# Power_Supply.net
KiCad netlist of a schematic drawn in Altium Designer
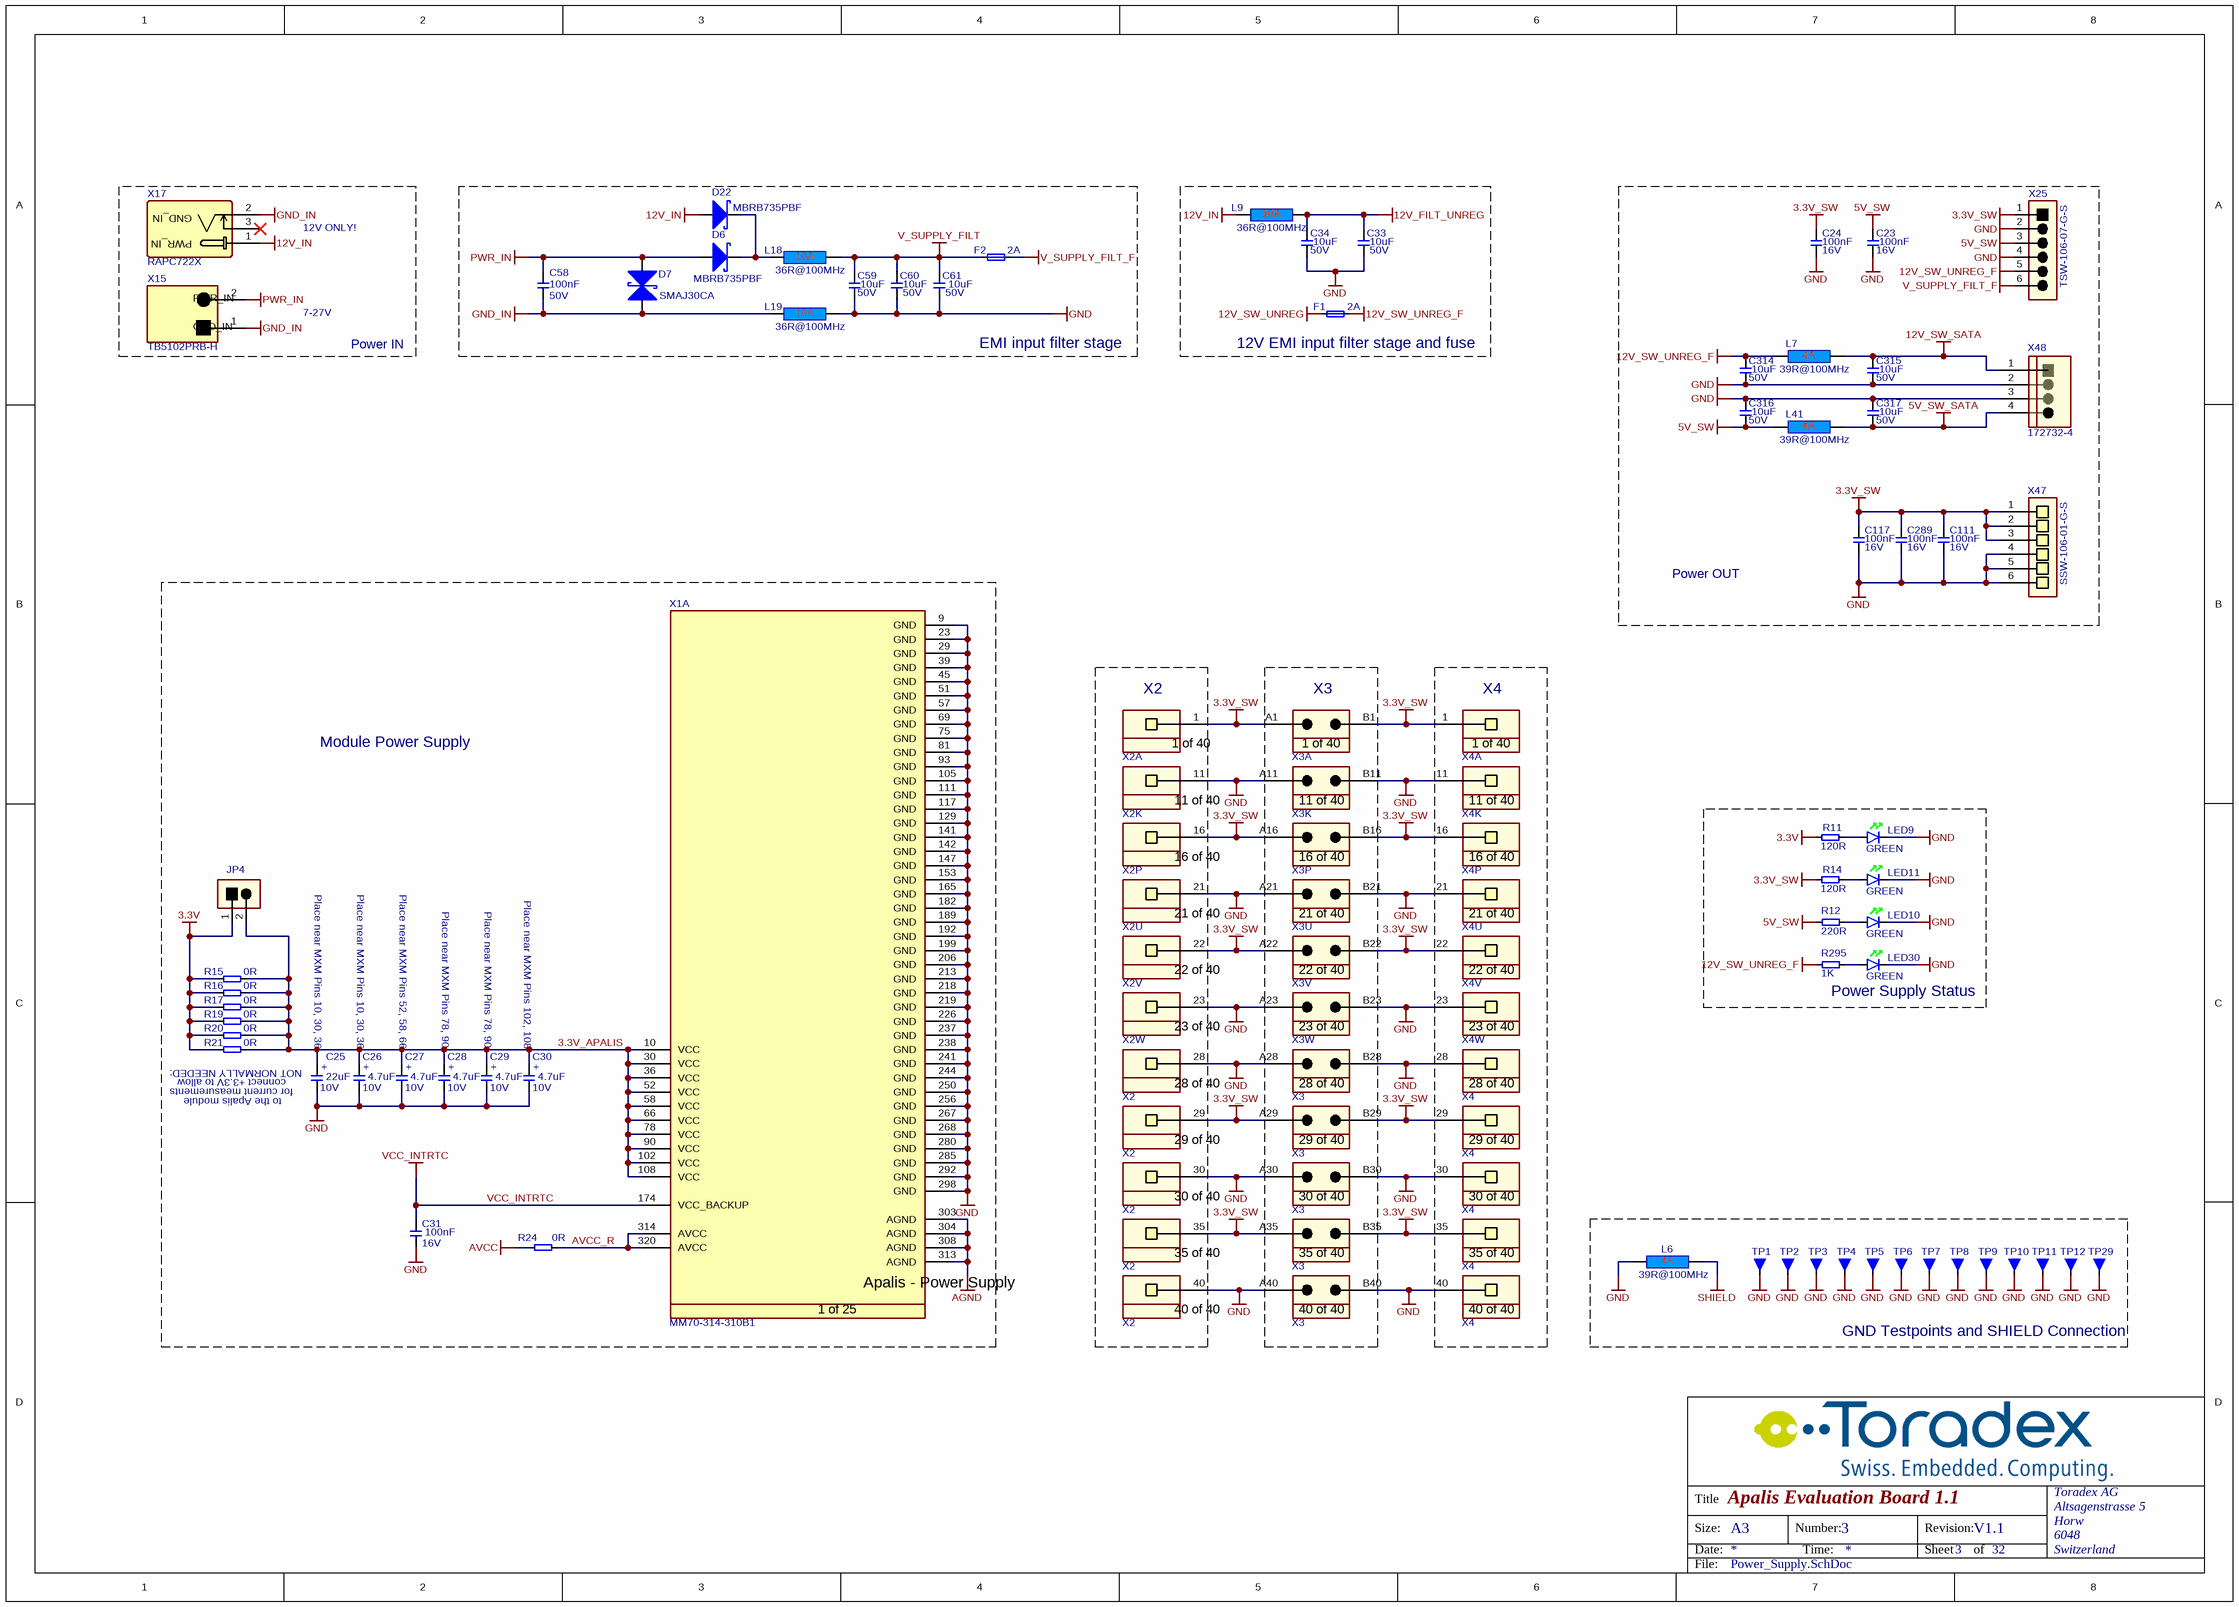
[diagram p0: Power_Supply.SchDoc]

(export (version "E")
  (design (tool "Eeschema 10.0.6"))
  (components
    (comp (ref "C23")
      (value "100nF")
      (footprint "T_CAPC0603X33N")
      (description "Capacitor Ceramic X7R 100nF 16V 10% 0603")
      (fields (field (name "TOLERANCE") "10%") (field (name "RATING") "16V"))
      (libsource (lib "Apalis Evaluation Board") (part "C-X7R-100nF-16V-10%-0603"))
    )
    (comp (ref "C24")
      (value "100nF")
      (footprint "T_CAPC0603X33N")
      (description "Capacitor Ceramic X7R 100nF 16V 10% 0603")
      (fields (field (name "TOLERANCE") "10%") (field (name "RATING") "16V"))
      (libsource (lib "Apalis Evaluation Board") (part "C-X7R-100nF-16V-10%-0603"))
    )
    (comp (ref "C25")
      (value "22uF")
      (footprint "CAPMP3528X210N")
      (description "Capacitor TA 22uF 10V 20% 3528")
      (fields (field (name "TOLERANCE") "20%") (field (name "RATING") "10V"))
      (libsource (lib "Apalis Evaluation Board") (part "C-TA-22uF-10V-20%-3528"))
    )
    (comp (ref "C26")
      (value "4.7uF")
      (footprint "T_CAPMP3216X180N")
      (description "Capacitor TA 4.7uF 10V 20% 3216")
      (fields (field (name "TOLERANCE") "20%") (field (name "RATING") "10V"))
      (libsource (lib "Apalis Evaluation Board") (part "C-TA-4.7uF-10V-20%-3216"))
    )
    (comp (ref "C27")
      (value "4.7uF")
      (footprint "T_CAPMP3216X180N")
      (description "Capacitor TA 4.7uF 10V 20% 3216")
      (fields (field (name "TOLERANCE") "20%") (field (name "RATING") "10V"))
      (libsource (lib "Apalis Evaluation Board") (part "C-TA-4.7uF-10V-20%-3216"))
    )
    (comp (ref "C28")
      (value "4.7uF")
      (footprint "T_CAPMP3216X180N")
      (description "Capacitor TA 4.7uF 10V 20% 3216")
      (fields (field (name "TOLERANCE") "20%") (field (name "RATING") "10V"))
      (libsource (lib "Apalis Evaluation Board") (part "C-TA-4.7uF-10V-20%-3216"))
    )
    (comp (ref "C29")
      (value "4.7uF")
      (footprint "T_CAPMP3216X180N")
      (description "Capacitor TA 4.7uF 10V 20% 3216")
      (fields (field (name "TOLERANCE") "20%") (field (name "RATING") "10V"))
      (libsource (lib "Apalis Evaluation Board") (part "C-TA-4.7uF-10V-20%-3216"))
    )
    (comp (ref "C30")
      (value "4.7uF")
      (footprint "T_CAPMP3216X180N")
      (description "Capacitor TA 4.7uF 10V 20% 3216")
      (fields (field (name "TOLERANCE") "20%") (field (name "RATING") "10V"))
      (libsource (lib "Apalis Evaluation Board") (part "C-TA-4.7uF-10V-20%-3216"))
    )
    (comp (ref "C31")
      (value "100nF")
      (footprint "T_CAPC0603X33N")
      (description "Capacitor Ceramic X7R 100nF 16V 10% 0603")
      (fields (field (name "TOLERANCE") "10%") (field (name "RATING") "16V"))
      (libsource (lib "Apalis Evaluation Board") (part "C-X7R-100nF-16V-10%-0603"))
    )
    (comp (ref "C33")
      (value "10uF")
      (footprint "CAPC3225X160N")
      (description "Capacitor Ceramic X5R 10uF 50V 20% 1210")
      (fields (field (name "TOLERANCE") "20%") (field (name "RATING") "50V"))
      (libsource (lib "Apalis Evaluation Board") (part "C-X5R-10uF-50V-20%-1210"))
    )
    (comp (ref "C34")
      (value "10uF")
      (footprint "CAPC3225X160N")
      (description "Capacitor Ceramic X5R 10uF 50V 20% 1210")
      (fields (field (name "TOLERANCE") "20%") (field (name "RATING") "50V"))
      (libsource (lib "Apalis Evaluation Board") (part "C-X5R-10uF-50V-20%-1210"))
    )
    (comp (ref "C58")
      (value "100nF")
      (footprint "T_CAPC0603X33N")
      (description "Capacitor Ceramic X7R 100nF 50V 20% 0603")
      (fields (field (name "TOLERANCE") "20%") (field (name "RATING") "50V"))
      (libsource (lib "Apalis Evaluation Board") (part "C-X7R-100nF-50V-20%-0603"))
    )
    (comp (ref "C59")
      (value "10uF")
      (footprint "CAPC3225X160N")
      (description "Capacitor Ceramic X5R 10uF 50V 20% 1210")
      (fields (field (name "TOLERANCE") "20%") (field (name "RATING") "50V"))
      (libsource (lib "Apalis Evaluation Board") (part "C-X5R-10uF-50V-20%-1210"))
    )
    (comp (ref "C60")
      (value "10uF")
      (footprint "CAPC3225X160N")
      (description "Capacitor Ceramic X5R 10uF 50V 20% 1210")
      (fields (field (name "TOLERANCE") "20%") (field (name "RATING") "50V"))
      (libsource (lib "Apalis Evaluation Board") (part "C-X5R-10uF-50V-20%-1210"))
    )
    (comp (ref "C61")
      (value "10uF")
      (footprint "CAPC3225X160N")
      (description "Capacitor Ceramic X5R 10uF 50V 20% 1210")
      (fields (field (name "TOLERANCE") "20%") (field (name "RATING") "50V"))
      (libsource (lib "Apalis Evaluation Board") (part "C-X5R-10uF-50V-20%-1210"))
    )
    (comp (ref "C111")
      (value "100nF")
      (footprint "T_CAPC0603X33N")
      (description "Capacitor Ceramic X7R 100nF 16V 10% 0603")
      (fields (field (name "TOLERANCE") "10%") (field (name "RATING") "16V"))
      (libsource (lib "Apalis Evaluation Board") (part "C-X7R-100nF-16V-10%-0603"))
    )
    (comp (ref "C117")
      (value "100nF")
      (footprint "T_CAPC0603X33N")
      (description "Capacitor Ceramic X7R 100nF 16V 10% 0603")
      (fields (field (name "TOLERANCE") "10%") (field (name "RATING") "16V"))
      (libsource (lib "Apalis Evaluation Board") (part "C-X7R-100nF-16V-10%-0603"))
    )
    (comp (ref "C289")
      (value "100nF")
      (footprint "T_CAPC0603X33N")
      (description "Capacitor Ceramic X7R 100nF 16V 10% 0603")
      (fields (field (name "TOLERANCE") "10%") (field (name "RATING") "16V"))
      (libsource (lib "Apalis Evaluation Board") (part "C-X7R-100nF-16V-10%-0603"))
    )
    (comp (ref "C314")
      (value "10uF")
      (footprint "CAPC3225X160N")
      (description "Capacitor Ceramic X5R 10uF 50V 20% 1210")
      (fields (field (name "TOLERANCE") "20%") (field (name "RATING") "50V"))
      (libsource (lib "Apalis Evaluation Board") (part "C-X5R-10uF-50V-20%-1210"))
    )
    (comp (ref "C315")
      (value "10uF")
      (footprint "CAPC3225X160N")
      (description "Capacitor Ceramic X5R 10uF 50V 20% 1210")
      (fields (field (name "TOLERANCE") "20%") (field (name "RATING") "50V"))
      (libsource (lib "Apalis Evaluation Board") (part "C-X5R-10uF-50V-20%-1210"))
    )
    (comp (ref "C316")
      (value "10uF")
      (footprint "CAPC3225X160N")
      (description "Capacitor Ceramic X5R 10uF 50V 20% 1210")
      (fields (field (name "TOLERANCE") "20%") (field (name "RATING") "50V"))
      (libsource (lib "Apalis Evaluation Board") (part "C-X5R-10uF-50V-20%-1210"))
    )
    (comp (ref "C317")
      (value "10uF")
      (footprint "CAPC3225X160N")
      (description "Capacitor Ceramic X5R 10uF 50V 20% 1210")
      (fields (field (name "TOLERANCE") "20%") (field (name "RATING") "50V"))
      (libsource (lib "Apalis Evaluation Board") (part "C-X5R-10uF-50V-20%-1210"))
    )
    (comp (ref "D6")
      (value "MBRB735PBF")
      (footprint "T_VISHAY_MBRB735PBF")
      (description "MBRB735PBF Schottky Diode")
      (fields (field (name "MANUFACTURER PART NO.") "MBRB735PBF"))
      (libsource (lib "Apalis Evaluation Board") (part "D-VISHAY-MBRB735PBF"))
    )
    (comp (ref "D7")
      (value "D-Littelfuse-SMAJ30CA-Schottky")
      (footprint "T_LITTLEFUSE_SMAJ30CA")
      (description "Bidirectional ESD protection")
      (fields (field (name "MANUFACTURER PART NO.") "SMAJ30CA"))
      (libsource (lib "Apalis Evaluation Board") (part "D-Littelfuse-SMAJ30CA-Schottky"))
    )
    (comp (ref "D22")
      (value "MBRB735PBF")
      (footprint "T_VISHAY_MBRB735PBF")
      (description "MBRB735PBF Schottky Diode")
      (fields (field (name "MANUFACTURER PART NO.") "MBRB735PBF"))
      (libsource (lib "Apalis Evaluation Board") (part "D-VISHAY-MBRB735PBF"))
    )
    (comp (ref "F1")
      (value "2A")
      (footprint "T_Littelfuse_0458")
      (description "Fuse 2A Fast")
      (fields (field (name "MANUFACTURER PART NO.") "0458002"))
      (libsource (lib "Apalis Evaluation Board") (part "F-Littelfuse-0458002"))
    )
    (comp (ref "F2")
      (value "2A")
      (footprint "T_Littelfuse_0458")
      (description "Fuse 2A Fast")
      (fields (field (name "MANUFACTURER PART NO.") "0458002"))
      (libsource (lib "Apalis Evaluation Board") (part "F-Littelfuse-0458002"))
    )
    (comp (ref "JP4")
      (value "TSW-101-07-G-D")
      (footprint "T_Samtec_TSW-101-07-G-D")
      (description "Header male, 1x2 Pins, 2.54 mm pitch")
      (libsource (lib "Apalis Evaluation Board") (part "CON-Samtec-TSW-101-07-G-D"))
    )
    (comp (ref "L6")
      (value "39R@100MHz")
      (footprint "INDC2013X130N")
      (description "39R@100MHz 4A EMI FILTER")
      (fields (field (name "TOLERANCE") "25%"))
      (libsource (lib "Apalis Evaluation Board") (part "L-Panasonic-EXC-ML20A390U-39R@100MHz-4A-25%-0805"))
    )
    (comp (ref "L7")
      (value "39R@100MHz")
      (footprint "INDC2013X130N")
      (description "39R@100MHz 4A EMI FILTER")
      (fields (field (name "TOLERANCE") "25%"))
      (libsource (lib "Apalis Evaluation Board") (part "L-Panasonic-EXC-ML20A390U-39R@100MHz-4A-25%-0805"))
    )
    (comp (ref "L9")
      (value "36R@100MHz")
      (footprint "T_Laird_35F0121-0SR-10")
      (description "Power Supply FB 10A")
      (fields (field (name "TOLERANCE") "25%"))
      (libsource (lib "Apalis Evaluation Board") (part "L-Laird-35F0121-0SR-10-10A-25%"))
    )
    (comp (ref "L18")
      (value "36R@100MHz")
      (footprint "T_Laird_35F0121-0SR-10")
      (description "Power Supply FB 10A")
      (fields (field (name "TOLERANCE") "25%"))
      (libsource (lib "Apalis Evaluation Board") (part "L-Laird-35F0121-0SR-10-10A-25%"))
    )
    (comp (ref "L19")
      (value "36R@100MHz")
      (footprint "T_Laird_35F0121-0SR-10")
      (description "Power Supply FB 10A")
      (fields (field (name "TOLERANCE") "25%"))
      (libsource (lib "Apalis Evaluation Board") (part "L-Laird-35F0121-0SR-10-10A-25%"))
    )
    (comp (ref "L41")
      (value "39R@100MHz")
      (footprint "INDC2013X130N")
      (description "39R@100MHz 4A EMI FILTER")
      (fields (field (name "TOLERANCE") "25%"))
      (libsource (lib "Apalis Evaluation Board") (part "L-Panasonic-EXC-ML20A390U-39R@100MHz-4A-25%-0805"))
    )
    (comp (ref "LED9")
      (value "LG T670-K1L2-1")
      (footprint "T_Osram_T670_GREEN")
      (description "LED green Osram LG T670-K1L2-1")
      (fields (field (name "COLOR") "GREEN"))
      (libsource (lib "Apalis Evaluation Board") (part "LED-Osram-T670-K1L2-1"))
    )
    (comp (ref "LED10")
      (value "LG T670-K1L2-1")
      (footprint "T_Osram_T670_GREEN")
      (description "LED green Osram LG T670-K1L2-1")
      (fields (field (name "COLOR") "GREEN"))
      (libsource (lib "Apalis Evaluation Board") (part "LED-Osram-T670-K1L2-1"))
    )
    (comp (ref "LED11")
      (value "LG T670-K1L2-1")
      (footprint "T_Osram_T670_GREEN")
      (description "LED green Osram LG T670-K1L2-1")
      (fields (field (name "COLOR") "GREEN"))
      (libsource (lib "Apalis Evaluation Board") (part "LED-Osram-T670-K1L2-1"))
    )
    (comp (ref "LED30")
      (value "LG T670-K1L2-1")
      (footprint "T_Osram_T670_GREEN")
      (description "LED green Osram LG T670-K1L2-1")
      (fields (field (name "COLOR") "GREEN"))
      (libsource (lib "Apalis Evaluation Board") (part "LED-Osram-T670-K1L2-1"))
    )
    (comp (ref "R11")
      (value "120R")
      (footprint "T_RESC0603X30N")
      (description "Resistor 120 ohm 63mW 5% 0603")
      (fields (field (name "TOLERANCE") "5%"))
      (libsource (lib "Apalis Evaluation Board") (part "R-120R-63mW-5%-0603"))
    )
    (comp (ref "R12")
      (value "220R")
      (footprint "T_RESC0603X30N")
      (description "Resistor 220 ohm 63mW 5% 0603")
      (fields (field (name "TOLERANCE") "5%"))
      (libsource (lib "Apalis Evaluation Board") (part "R-220R-63mW-5%-0603"))
    )
    (comp (ref "R14")
      (value "120R")
      (footprint "T_RESC0603X30N")
      (description "Resistor 120 ohm 63mW 5% 0603")
      (fields (field (name "TOLERANCE") "5%"))
      (libsource (lib "Apalis Evaluation Board") (part "R-120R-63mW-5%-0603"))
    )
    (comp (ref "R15")
      (value "0R")
      (footprint "T_RESC3216X760N")
      (description "Resistor 0 ohm 63mW 1% 1206")
      (fields (field (name "TOLERANCE") "1%"))
      (libsource (lib "Apalis Evaluation Board") (part "R-0R-63mW-1%-1206"))
    )
    (comp (ref "R16")
      (value "0R")
      (footprint "T_RESC3216X760N")
      (description "Resistor 0 ohm 63mW 1% 1206")
      (fields (field (name "TOLERANCE") "1%"))
      (libsource (lib "Apalis Evaluation Board") (part "R-0R-63mW-1%-1206"))
    )
    (comp (ref "R17")
      (value "0R")
      (footprint "T_RESC3216X760N")
      (description "Resistor 0 ohm 63mW 1% 1206")
      (fields (field (name "TOLERANCE") "1%"))
      (libsource (lib "Apalis Evaluation Board") (part "R-0R-63mW-1%-1206"))
    )
    (comp (ref "R19")
      (value "0R")
      (footprint "T_RESC3216X760N")
      (description "Resistor 0 ohm 63mW 1% 1206")
      (fields (field (name "TOLERANCE") "1%"))
      (libsource (lib "Apalis Evaluation Board") (part "R-0R-63mW-1%-1206"))
    )
    (comp (ref "R20")
      (value "0R")
      (footprint "T_RESC3216X760N")
      (description "Resistor 0 ohm 63mW 1% 1206")
      (fields (field (name "TOLERANCE") "1%"))
      (libsource (lib "Apalis Evaluation Board") (part "R-0R-63mW-1%-1206"))
    )
    (comp (ref "R21")
      (value "0R")
      (footprint "T_RESC3216X760N")
      (description "Resistor 0 ohm 63mW 1% 1206")
      (fields (field (name "TOLERANCE") "1%"))
      (libsource (lib "Apalis Evaluation Board") (part "R-0R-63mW-1%-1206"))
    )
    (comp (ref "R24")
      (value "0R")
      (footprint "T_RESC0603X30N")
      (description "Resistor 0 ohm 63mW 1% 0603")
      (fields (field (name "TOLERANCE") "1%"))
      (libsource (lib "Apalis Evaluation Board") (part "R-0R-63mW-1%-0603"))
    )
    (comp (ref "R295")
      (value "1K")
      (footprint "T_RESC0603X30N")
      (description "Resistor 1 Kohm 63mW 5% 0603")
      (fields (field (name "TOLERANCE") "5%"))
      (libsource (lib "Apalis Evaluation Board") (part "R-1KR-63mW-5%-0603"))
    )
    (comp (ref "TP1")
      (value "5011")
      (footprint "T_TP-THT - EYE")
      (description "Testpin Eye TH")
      (libsource (lib "Apalis Evaluation Board") (part "TP-Keystone-5011"))
    )
    (comp (ref "TP2")
      (value "5011")
      (footprint "T_TP-THT - EYE")
      (description "Testpin Eye TH")
      (libsource (lib "Apalis Evaluation Board") (part "TP-Keystone-5011"))
    )
    (comp (ref "TP3")
      (value "5011")
      (footprint "T_TP-THT - EYE")
      (description "Testpin Eye TH")
      (libsource (lib "Apalis Evaluation Board") (part "TP-Keystone-5011"))
    )
    (comp (ref "TP4")
      (value "5011")
      (footprint "T_TP-THT - EYE")
      (description "Testpin Eye TH")
      (libsource (lib "Apalis Evaluation Board") (part "TP-Keystone-5011"))
    )
    (comp (ref "TP5")
      (value "5011")
      (footprint "T_TP-THT - EYE")
      (description "Testpin Eye TH")
      (libsource (lib "Apalis Evaluation Board") (part "TP-Keystone-5011"))
    )
    (comp (ref "TP6")
      (value "5011")
      (footprint "T_TP-THT - EYE")
      (description "Testpin Eye TH")
      (libsource (lib "Apalis Evaluation Board") (part "TP-Keystone-5011"))
    )
    (comp (ref "TP7")
      (value "5011")
      (footprint "T_TP-THT - EYE")
      (description "Testpin Eye TH")
      (libsource (lib "Apalis Evaluation Board") (part "TP-Keystone-5011"))
    )
    (comp (ref "TP8")
      (value "5011")
      (footprint "T_TP-THT - EYE")
      (description "Testpin Eye TH")
      (libsource (lib "Apalis Evaluation Board") (part "TP-Keystone-5011"))
    )
    (comp (ref "TP9")
      (value "5011")
      (footprint "T_TP-THT - EYE")
      (description "Testpin Eye TH")
      (libsource (lib "Apalis Evaluation Board") (part "TP-Keystone-5011"))
    )
    (comp (ref "TP10")
      (value "5011")
      (footprint "T_TP-THT - EYE")
      (description "Testpin Eye TH")
      (libsource (lib "Apalis Evaluation Board") (part "TP-Keystone-5011"))
    )
    (comp (ref "TP11")
      (value "5011")
      (footprint "T_TP-THT - EYE")
      (description "Testpin Eye TH")
      (libsource (lib "Apalis Evaluation Board") (part "TP-Keystone-5011"))
    )
    (comp (ref "TP12")
      (value "5011")
      (footprint "T_TP-THT - EYE")
      (description "Testpin Eye TH")
      (libsource (lib "Apalis Evaluation Board") (part "TP-Keystone-5011"))
    )
    (comp (ref "TP29")
      (value "5011")
      (footprint "T_TP-THT - EYE")
      (description "Testpin Eye TH")
      (libsource (lib "Apalis Evaluation Board") (part "TP-Keystone-5011"))
    )
    (comp (ref "X1")
      (value "CON-JAE-MM70-314-310B1-314-0.5mm")
      (footprint "T_JAE_MM70-314-310B1")
      (description "MXM3 Connector")
      (fields (field (name "MANUFACTURER PART NO.") "MM70-314-310B1"))
      (libsource (lib "Apalis Evaluation Board") (part "CON-JAE-MM70-314-310B1-314-0.5mm"))
    )
    (comp (ref "X2")
      (value "SSW-110-01-G-S")
      (footprint "T_Samtec_SSW-110-01-G-S")
      (description "Receptacle Female Socket 1x40 pin 2.54mm pitch")
      (libsource (lib "Apalis Evaluation Board") (part "CON-Samtec-SSW-110-01-G-S"))
    )
    (comp (ref "X3")
      (value "TSW-110-07-G-D")
      (footprint "T_Samtec_TSW-110-07-G-D")
      (description "Header 2x40 pin 2.54mm pitch")
      (libsource (lib "Apalis Evaluation Board") (part "CON-Samtec-TSW-110-07-G-D"))
    )
    (comp (ref "X4")
      (value "SSW-110-01-G-S")
      (footprint "T_Samtec_SSW-110-01-G-S")
      (description "Receptacle Female Socket 1x40 pin 2.54mm pitch")
      (libsource (lib "") (part "CON-Samtec-SSW-110-01-G-S_1"))
    )
    (comp (ref "X15")
      (value "TB5102PRB-H")
      (footprint "T_AUK_TB5102PRB-H")
      (description "Power Connector")
      (fields (field (name "MANUFACTURER PART NO.") "TB5102PRB-H"))
      (libsource (lib "Apalis Evaluation Board") (part "CON-AUK-TB5102PRB-H-1x2-50.8mm"))
    )
    (comp (ref "X17")
      (value "RAPC722X")
      (footprint "T_DCJ20-0014TB-L")
      (description "Power Jack")
      (fields (field (name "MANUFACTURER PART NO.") "RAPC722X"))
      (libsource (lib "Apalis Evaluation Board") (part "CON-SWC-RAPC722X"))
    )
    (comp (ref "X25")
      (value "TSW-106-07-G-S")
      (footprint "T_samtech_TSW-106-07-G-S")
      (description "Header male, 1X6 Pins, 2.54 mm pitch")
      (fields (field (name "MANUFACTURER PART NO.") "TSW-106-07-G-S"))
      (libsource (lib "Apalis Evaluation Board") (part "CON-Samtec-TSW-106-07-G-S"))
    )
    (comp (ref "X47")
      (value "SSW-106-01-G-S")
      (footprint "T_samtech_SSW-106-01-G-S")
      (description "Receptacle Female Socket, 1x6 Pins, 2.54mm pitch")
      (fields (field (name "MANUFACTURER PART NO.") "SSW-106-01-G-S"))
      (libsource (lib "Apalis Evaluation Board") (part "CON-Samtec-SSW-106-01-G-S"))
    )
    (comp (ref "X48")
      (value "172732-4")
      (footprint "T_TE_172732-4")
      (description "Header 4 pos Vert Kink Pin")
      (fields (field (name "MANUFACTURER PART NO.") "172732-4"))
      (libsource (lib "Apalis Evaluation Board") (part "CON-TECon-172732-4"))
    )
  )
  (nets
    (net (code "1") (name "/3.3V_APALIS") (class "Default")
      (node (ref "C25") (pin "1") (pinfunction "1_1") (pintype "passive"))
      (node (ref "C26") (pin "1") (pinfunction "1_1") (pintype "passive"))
      (node (ref "C27") (pin "1") (pinfunction "1_1") (pintype "passive"))
      (node (ref "C28") (pin "1") (pinfunction "1_1") (pintype "passive"))
      (node (ref "C29") (pin "1") (pinfunction "1_1") (pintype "passive"))
      (node (ref "C30") (pin "1") (pinfunction "1_1") (pintype "passive"))
      (node (ref "JP4") (pin "2") (pinfunction "2_2") (pintype "passive"))
      (node (ref "R15") (pin "2") (pinfunction "2_2") (pintype "passive"))
      (node (ref "R16") (pin "2") (pinfunction "2_2") (pintype "passive"))
      (node (ref "R17") (pin "2") (pinfunction "2_2") (pintype "passive"))
      (node (ref "R19") (pin "2") (pinfunction "2_2") (pintype "passive"))
      (node (ref "R20") (pin "2") (pinfunction "2_2") (pintype "passive"))
      (node (ref "R21") (pin "2") (pinfunction "2_2") (pintype "passive"))
      (node (ref "X1") (pin "10") (pinfunction "VCC_10") (pintype "passive"))
      (node (ref "X1") (pin "102") (pinfunction "VCC_102") (pintype "passive"))
      (node (ref "X1") (pin "108") (pinfunction "VCC_108") (pintype "passive"))
      (node (ref "X1") (pin "30") (pinfunction "VCC_30") (pintype "passive"))
      (node (ref "X1") (pin "36") (pinfunction "VCC_36") (pintype "passive"))
      (node (ref "X1") (pin "52") (pinfunction "VCC_52") (pintype "passive"))
      (node (ref "X1") (pin "58") (pinfunction "VCC_58") (pintype "passive"))
      (node (ref "X1") (pin "66") (pinfunction "VCC_66") (pintype "passive"))
      (node (ref "X1") (pin "78") (pinfunction "VCC_78") (pintype "passive"))
      (node (ref "X1") (pin "90") (pinfunction "VCC_90") (pintype "passive"))
    )
    (net (code "2") (name "/AVCC_R") (class "Default")
      (node (ref "R24") (pin "2") (pinfunction "2_2") (pintype "passive"))
      (node (ref "X1") (pin "314") (pinfunction "AVCC_314") (pintype "power_in"))
      (node (ref "X1") (pin "320") (pinfunction "AVCC_320") (pintype "passive"))
    )
    (net (code "3") (name "3.3V") (class "Default")
      (node (ref "JP4") (pin "1") (pinfunction "1_1") (pintype "passive"))
      (node (ref "R11") (pin "1") (pinfunction "1_1") (pintype "passive"))
      (node (ref "R15") (pin "1") (pinfunction "1_1") (pintype "passive"))
      (node (ref "R16") (pin "1") (pinfunction "1_1") (pintype "passive"))
      (node (ref "R17") (pin "1") (pinfunction "1_1") (pintype "passive"))
      (node (ref "R19") (pin "1") (pinfunction "1_1") (pintype "passive"))
      (node (ref "R20") (pin "1") (pinfunction "1_1") (pintype "passive"))
      (node (ref "R21") (pin "1") (pinfunction "1_1") (pintype "passive"))
    )
    (net (code "4") (name "3.3V_SW") (class "Default")
      (node (ref "C111") (pin "2") (pinfunction "2_2") (pintype "passive"))
      (node (ref "C117") (pin "2") (pinfunction "2_2") (pintype "passive"))
      (node (ref "C24") (pin "2") (pinfunction "2_2") (pintype "passive"))
      (node (ref "C289") (pin "2") (pinfunction "2_2") (pintype "passive"))
      (node (ref "R14") (pin "1") (pinfunction "1_1") (pintype "passive"))
      (node (ref "X2") (pin "1") (pinfunction "1_1") (pintype "passive"))
      (node (ref "X2") (pin "16") (pinfunction "16_16") (pintype "passive"))
      (node (ref "X2") (pin "22") (pinfunction "22_22") (pintype "passive"))
      (node (ref "X2") (pin "29") (pinfunction "29_29") (pintype "passive"))
      (node (ref "X2") (pin "35") (pinfunction "35_35") (pintype "passive"))
      (node (ref "X25") (pin "1") (pinfunction "1_1") (pintype "passive"))
      (node (ref "X3") (pin "A1") (pinfunction "A1_A1") (pintype "passive"))
      (node (ref "X3") (pin "A16") (pinfunction "A16_A16") (pintype "passive"))
      (node (ref "X3") (pin "A22") (pinfunction "A22_A22") (pintype "passive"))
      (node (ref "X3") (pin "A29") (pinfunction "A29_A29") (pintype "passive"))
      (node (ref "X3") (pin "A35") (pinfunction "A35_A35") (pintype "passive"))
      (node (ref "X3") (pin "B1") (pinfunction "B1_B1") (pintype "passive"))
      (node (ref "X3") (pin "B16") (pinfunction "B16_B16") (pintype "passive"))
      (node (ref "X3") (pin "B22") (pinfunction "B22_B22") (pintype "passive"))
      (node (ref "X3") (pin "B29") (pinfunction "B29_B29") (pintype "passive"))
      (node (ref "X3") (pin "B35") (pinfunction "B35_B35") (pintype "passive"))
      (node (ref "X4") (pin "1") (pinfunction "1_1") (pintype "passive"))
      (node (ref "X4") (pin "16") (pinfunction "16_16") (pintype "passive"))
      (node (ref "X4") (pin "22") (pinfunction "22_22") (pintype "passive"))
      (node (ref "X4") (pin "29") (pinfunction "29_29") (pintype "passive"))
      (node (ref "X4") (pin "35") (pinfunction "35_35") (pintype "passive"))
      (node (ref "X47") (pin "1") (pinfunction "1_1") (pintype "passive"))
      (node (ref "X47") (pin "2") (pinfunction "2_2") (pintype "passive"))
      (node (ref "X47") (pin "3") (pinfunction "3_3") (pintype "passive"))
    )
    (net (code "5") (name "5V_SW") (class "Default")
      (node (ref "C23") (pin "1") (pinfunction "1_1") (pintype "passive"))
      (node (ref "C316") (pin "1") (pinfunction "1_1") (pintype "passive"))
      (node (ref "L41") (pin "1") (pinfunction "1_1") (pintype "passive"))
      (node (ref "R12") (pin "1") (pinfunction "1_1") (pintype "passive"))
      (node (ref "X25") (pin "3") (pinfunction "3_3") (pintype "passive"))
    )
    (net (code "6") (name "5V_SW_SATA") (class "Default")
      (node (ref "C317") (pin "1") (pinfunction "1_1") (pintype "passive"))
      (node (ref "L41") (pin "2") (pinfunction "2_2") (pintype "passive"))
      (node (ref "X48") (pin "4") (pinfunction "5V_4") (pintype "power_in"))
    )
    (net (code "7") (name "12V_FILT_UNREG") (class "Default")
      (node (ref "C33") (pin "2") (pinfunction "2_2") (pintype "passive"))
      (node (ref "C34") (pin "2") (pinfunction "2_2") (pintype "passive"))
      (node (ref "L9") (pin "2") (pinfunction "2_2") (pintype "passive"))
    )
    (net (code "8") (name "12V_IN") (class "Default")
      (node (ref "D22") (pin "3") (pinfunction "3_3") (pintype "passive"))
      (node (ref "L9") (pin "1") (pinfunction "1_1") (pintype "passive"))
      (node (ref "X17") (pin "1") (pinfunction "GND_IN_1") (pintype "passive"))
    )
    (net (code "9") (name "12V_SW_SATA") (class "Default")
      (node (ref "C315") (pin "2") (pinfunction "2_2") (pintype "passive"))
      (node (ref "L7") (pin "2") (pinfunction "2_2") (pintype "passive"))
      (node (ref "X48") (pin "1") (pinfunction "12V_1") (pintype "power_in"))
    )
    (net (code "10") (name "12V_SW_UNREG") (class "Default")
      (node (ref "F1") (pin "1") (pinfunction "1_1") (pintype "passive"))
    )
    (net (code "11") (name "12V_SW_UNREG_F") (class "Default")
      (node (ref "C314") (pin "2") (pinfunction "2_2") (pintype "passive"))
      (node (ref "F1") (pin "2") (pinfunction "2_2") (pintype "passive"))
      (node (ref "L7") (pin "1") (pinfunction "1_1") (pintype "passive"))
      (node (ref "R295") (pin "1") (pinfunction "1_1") (pintype "passive"))
      (node (ref "X25") (pin "5") (pinfunction "5_5") (pintype "passive"))
    )
    (net (code "12") (name "AGND") (class "Default")
      (node (ref "X1") (pin "303") (pinfunction "AGND_303") (pintype "power_in"))
      (node (ref "X1") (pin "304") (pinfunction "AGND_304") (pintype "power_in"))
      (node (ref "X1") (pin "308") (pinfunction "AGND_308") (pintype "power_in"))
      (node (ref "X1") (pin "313") (pinfunction "AGND_313") (pintype "passive"))
    )
    (net (code "13") (name "AVCC") (class "Default")
      (node (ref "R24") (pin "1") (pinfunction "1_1") (pintype "passive"))
    )
    (net (code "14") (name "GND") (class "Default")
      (node (ref "C111") (pin "1") (pinfunction "1_1") (pintype "passive"))
      (node (ref "C117") (pin "1") (pinfunction "1_1") (pintype "passive"))
      (node (ref "C23") (pin "2") (pinfunction "2_2") (pintype "passive"))
      (node (ref "C24") (pin "1") (pinfunction "1_1") (pintype "passive"))
      (node (ref "C25") (pin "2") (pinfunction "2_2") (pintype "passive"))
      (node (ref "C26") (pin "2") (pinfunction "2_2") (pintype "passive"))
      (node (ref "C27") (pin "2") (pinfunction "2_2") (pintype "passive"))
      (node (ref "C28") (pin "2") (pinfunction "2_2") (pintype "passive"))
      (node (ref "C289") (pin "1") (pinfunction "1_1") (pintype "passive"))
      (node (ref "C29") (pin "2") (pinfunction "2_2") (pintype "passive"))
      (node (ref "C30") (pin "2") (pinfunction "2_2") (pintype "passive"))
      (node (ref "C31") (pin "1") (pinfunction "1_1") (pintype "passive"))
      (node (ref "C314") (pin "1") (pinfunction "1_1") (pintype "passive"))
      (node (ref "C315") (pin "1") (pinfunction "1_1") (pintype "passive"))
      (node (ref "C316") (pin "2") (pinfunction "2_2") (pintype "passive"))
      (node (ref "C317") (pin "2") (pinfunction "2_2") (pintype "passive"))
      (node (ref "C33") (pin "1") (pinfunction "1_1") (pintype "passive"))
      (node (ref "C34") (pin "1") (pinfunction "1_1") (pintype "passive"))
      (node (ref "C59") (pin "1") (pinfunction "1_1") (pintype "passive"))
      (node (ref "C60") (pin "1") (pinfunction "1_1") (pintype "passive"))
      (node (ref "C61") (pin "1") (pinfunction "1_1") (pintype "passive"))
      (node (ref "L19") (pin "2") (pinfunction "2_2") (pintype "passive"))
      (node (ref "L6") (pin "1") (pinfunction "1_1") (pintype "passive"))
      (node (ref "LED10") (pin "K") (pinfunction "K_K") (pintype "passive"))
      (node (ref "LED11") (pin "K") (pinfunction "K_K") (pintype "passive"))
      (node (ref "LED30") (pin "K") (pinfunction "K_K") (pintype "passive"))
      (node (ref "LED9") (pin "K") (pinfunction "K_K") (pintype "passive"))
      (node (ref "TP1") (pin "1") (pinfunction "1_1") (pintype "passive"))
      (node (ref "TP10") (pin "1") (pinfunction "1_1") (pintype "passive"))
      (node (ref "TP11") (pin "1") (pinfunction "1_1") (pintype "passive"))
      (node (ref "TP12") (pin "1") (pinfunction "1_1") (pintype "passive"))
      (node (ref "TP2") (pin "1") (pinfunction "1_1") (pintype "passive"))
      (node (ref "TP29") (pin "1") (pinfunction "1_1") (pintype "passive"))
      (node (ref "TP3") (pin "1") (pinfunction "1_1") (pintype "passive"))
      (node (ref "TP4") (pin "1") (pinfunction "1_1") (pintype "passive"))
      (node (ref "TP5") (pin "1") (pinfunction "1_1") (pintype "passive"))
      (node (ref "TP6") (pin "1") (pinfunction "1_1") (pintype "passive"))
      (node (ref "TP7") (pin "1") (pinfunction "1_1") (pintype "passive"))
      (node (ref "TP8") (pin "1") (pinfunction "1_1") (pintype "passive"))
      (node (ref "TP9") (pin "1") (pinfunction "1_1") (pintype "passive"))
      (node (ref "X1") (pin "105") (pinfunction "GND_105") (pintype "power_in"))
      (node (ref "X1") (pin "111") (pinfunction "GND_111") (pintype "power_in"))
      (node (ref "X1") (pin "117") (pinfunction "GND_117") (pintype "power_in"))
      (node (ref "X1") (pin "129") (pinfunction "GND_129") (pintype "power_in"))
      (node (ref "X1") (pin "141") (pinfunction "GND_141") (pintype "power_in"))
      (node (ref "X1") (pin "142") (pinfunction "GND_142") (pintype "power_in"))
      (node (ref "X1") (pin "147") (pinfunction "GND_147") (pintype "power_in"))
      (node (ref "X1") (pin "153") (pinfunction "GND_153") (pintype "power_in"))
      (node (ref "X1") (pin "165") (pinfunction "GND_165") (pintype "power_in"))
      (node (ref "X1") (pin "182") (pinfunction "GND_182") (pintype "power_in"))
      (node (ref "X1") (pin "189") (pinfunction "GND_189") (pintype "power_in"))
      (node (ref "X1") (pin "192") (pinfunction "GND_192") (pintype "power_in"))
      (node (ref "X1") (pin "199") (pinfunction "GND_199") (pintype "power_in"))
      (node (ref "X1") (pin "206") (pinfunction "GND_206") (pintype "power_in"))
      (node (ref "X1") (pin "213") (pinfunction "GND_213") (pintype "power_in"))
      (node (ref "X1") (pin "218") (pinfunction "GND_218") (pintype "power_in"))
      (node (ref "X1") (pin "219") (pinfunction "GND_219") (pintype "power_in"))
      (node (ref "X1") (pin "226") (pinfunction "GND_226") (pintype "power_in"))
      (node (ref "X1") (pin "23") (pinfunction "GND_23") (pintype "passive"))
      (node (ref "X1") (pin "237") (pinfunction "GND_237") (pintype "power_in"))
      (node (ref "X1") (pin "238") (pinfunction "GND_238") (pintype "power_in"))
      (node (ref "X1") (pin "241") (pinfunction "GND_241") (pintype "power_in"))
      (node (ref "X1") (pin "244") (pinfunction "GND_244") (pintype "power_in"))
      (node (ref "X1") (pin "250") (pinfunction "GND_250") (pintype "power_in"))
      (node (ref "X1") (pin "256") (pinfunction "GND_256") (pintype "power_in"))
      (node (ref "X1") (pin "267") (pinfunction "GND_267") (pintype "power_in"))
      (node (ref "X1") (pin "268") (pinfunction "GND_268") (pintype "power_in"))
      (node (ref "X1") (pin "280") (pinfunction "GND_280") (pintype "power_in"))
      (node (ref "X1") (pin "285") (pinfunction "GND_285") (pintype "power_in"))
      (node (ref "X1") (pin "29") (pinfunction "GND_29") (pintype "power_in"))
      (node (ref "X1") (pin "292") (pinfunction "GND_292") (pintype "power_in"))
      (node (ref "X1") (pin "298") (pinfunction "GND_298") (pintype "power_in"))
      (node (ref "X1") (pin "39") (pinfunction "GND_39") (pintype "power_in"))
      (node (ref "X1") (pin "45") (pinfunction "GND_45") (pintype "power_in"))
      (node (ref "X1") (pin "51") (pinfunction "GND_51") (pintype "power_in"))
      (node (ref "X1") (pin "57") (pinfunction "GND_57") (pintype "power_in"))
      (node (ref "X1") (pin "69") (pinfunction "GND_69") (pintype "power_in"))
      (node (ref "X1") (pin "75") (pinfunction "GND_75") (pintype "power_in"))
      (node (ref "X1") (pin "81") (pinfunction "GND_81") (pintype "power_in"))
      (node (ref "X1") (pin "9") (pinfunction "GND_9") (pintype "passive"))
      (node (ref "X1") (pin "93") (pinfunction "GND_93") (pintype "power_in"))
      (node (ref "X2") (pin "11") (pinfunction "11_11") (pintype "passive"))
      (node (ref "X2") (pin "21") (pinfunction "21_21") (pintype "passive"))
      (node (ref "X2") (pin "23") (pinfunction "23_23") (pintype "passive"))
      (node (ref "X2") (pin "28") (pinfunction "28_28") (pintype "passive"))
      (node (ref "X2") (pin "30") (pinfunction "30_30") (pintype "passive"))
      (node (ref "X2") (pin "40") (pinfunction "40_40") (pintype "passive"))
      (node (ref "X25") (pin "2") (pinfunction "2_2") (pintype "passive"))
      (node (ref "X25") (pin "4") (pinfunction "4_4") (pintype "passive"))
      (node (ref "X3") (pin "A11") (pinfunction "A11_A11") (pintype "passive"))
      (node (ref "X3") (pin "A21") (pinfunction "A21_A21") (pintype "passive"))
      (node (ref "X3") (pin "A23") (pinfunction "A23_A23") (pintype "passive"))
      (node (ref "X3") (pin "A28") (pinfunction "A28_A28") (pintype "passive"))
      (node (ref "X3") (pin "A30") (pinfunction "A30_A30") (pintype "passive"))
      (node (ref "X3") (pin "A40") (pinfunction "A40_A40") (pintype "passive"))
      (node (ref "X3") (pin "B11") (pinfunction "B11_B11") (pintype "passive"))
      (node (ref "X3") (pin "B21") (pinfunction "B21_B21") (pintype "passive"))
      (node (ref "X3") (pin "B23") (pinfunction "B23_B23") (pintype "passive"))
      (node (ref "X3") (pin "B28") (pinfunction "B28_B28") (pintype "passive"))
      (node (ref "X3") (pin "B30") (pinfunction "B30_B30") (pintype "passive"))
      (node (ref "X3") (pin "B40") (pinfunction "B40_B40") (pintype "passive"))
      (node (ref "X4") (pin "11") (pinfunction "11_11") (pintype "passive"))
      (node (ref "X4") (pin "21") (pinfunction "21_21") (pintype "passive"))
      (node (ref "X4") (pin "23") (pinfunction "23_23") (pintype "passive"))
      (node (ref "X4") (pin "28") (pinfunction "28_28") (pintype "passive"))
      (node (ref "X4") (pin "30") (pinfunction "30_30") (pintype "passive"))
      (node (ref "X4") (pin "40") (pinfunction "40_40") (pintype "passive"))
      (node (ref "X47") (pin "4") (pinfunction "4_4") (pintype "passive"))
      (node (ref "X47") (pin "5") (pinfunction "5_5") (pintype "passive"))
      (node (ref "X47") (pin "6") (pinfunction "6_6") (pintype "passive"))
      (node (ref "X48") (pin "2") (pinfunction "GND_2") (pintype "passive"))
      (node (ref "X48") (pin "3") (pinfunction "GND_3") (pintype "passive"))
    )
    (net (code "15") (name "GND_IN") (class "Default")
      (node (ref "C58") (pin "1") (pinfunction "1_1") (pintype "passive"))
      (node (ref "D7") (pin "2") (pinfunction "Anode_2") (pintype "passive"))
      (node (ref "L19") (pin "1") (pinfunction "1_1") (pintype "passive"))
      (node (ref "X15") (pin "1") (pinfunction "GND_IN_1") (pintype "passive"))
      (node (ref "X17") (pin "2") (pinfunction "PWR_IN_2") (pintype "passive"))
    )
    (net (code "16") (name "Net-(D22-Pad2)") (class "Default")
      (node (ref "D22") (pin "2") (pinfunction "2_2") (pintype "passive"))
      (node (ref "D6") (pin "2") (pinfunction "2_2") (pintype "passive"))
      (node (ref "L18") (pin "1") (pinfunction "1_1") (pintype "passive"))
    )
    (net (code "17") (name "Net-(LED9-PadA)") (class "Default")
      (node (ref "LED9") (pin "A") (pinfunction "A_A") (pintype "passive"))
      (node (ref "R11") (pin "2") (pinfunction "2_2") (pintype "passive"))
    )
    (net (code "18") (name "Net-(LED10-PadA)") (class "Default")
      (node (ref "LED10") (pin "A") (pinfunction "A_A") (pintype "passive"))
      (node (ref "R12") (pin "2") (pinfunction "2_2") (pintype "passive"))
    )
    (net (code "19") (name "Net-(LED11-PadA)") (class "Default")
      (node (ref "LED11") (pin "A") (pinfunction "A_A") (pintype "passive"))
      (node (ref "R14") (pin "2") (pinfunction "2_2") (pintype "passive"))
    )
    (net (code "20") (name "Net-(LED30-PadA)") (class "Default")
      (node (ref "LED30") (pin "A") (pinfunction "A_A") (pintype "passive"))
      (node (ref "R295") (pin "2") (pinfunction "2_2") (pintype "passive"))
    )
    (net (code "21") (name "PWR_IN") (class "Default")
      (node (ref "C58") (pin "2") (pinfunction "2_2") (pintype "passive"))
      (node (ref "D6") (pin "3") (pinfunction "3_3") (pintype "passive"))
      (node (ref "D7") (pin "1") (pinfunction "Cathode_1") (pintype "passive"))
      (node (ref "X15") (pin "2") (pinfunction "PWR_IN_2") (pintype "passive"))
    )
    (net (code "22") (name "SHIELD") (class "Default")
      (node (ref "L6") (pin "2") (pinfunction "2_2") (pintype "passive"))
    )
    (net (code "23") (name "VCC_INTRTC") (class "Default")
      (node (ref "C31") (pin "2") (pinfunction "2_2") (pintype "passive"))
      (node (ref "X1") (pin "174") (pinfunction "VCC_BACKUP_174") (pintype "passive"))
    )
    (net (code "24") (name "V_SUPPLY_FILT") (class "Default")
      (node (ref "C59") (pin "2") (pinfunction "2_2") (pintype "passive"))
      (node (ref "C60") (pin "2") (pinfunction "2_2") (pintype "passive"))
      (node (ref "C61") (pin "2") (pinfunction "2_2") (pintype "passive"))
      (node (ref "F2") (pin "1") (pinfunction "1_1") (pintype "passive"))
      (node (ref "L18") (pin "2") (pinfunction "2_2") (pintype "passive"))
    )
    (net (code "25") (name "V_SUPPLY_FILT_F") (class "Default")
      (node (ref "F2") (pin "2") (pinfunction "2_2") (pintype "passive"))
      (node (ref "X25") (pin "6") (pinfunction "6_6") (pintype "passive"))
    )
    (net (code "26") (name "unconnected-(X17-PWR_IN-Pad3)") (class "Default")
      (node (ref "X17") (pin "3") (pinfunction "PWR_IN_3") (pintype "passive+no_connect"))
    )
  )
)
